# self-balan.net
KiCad netlist of a schematic drawn in EAGLE
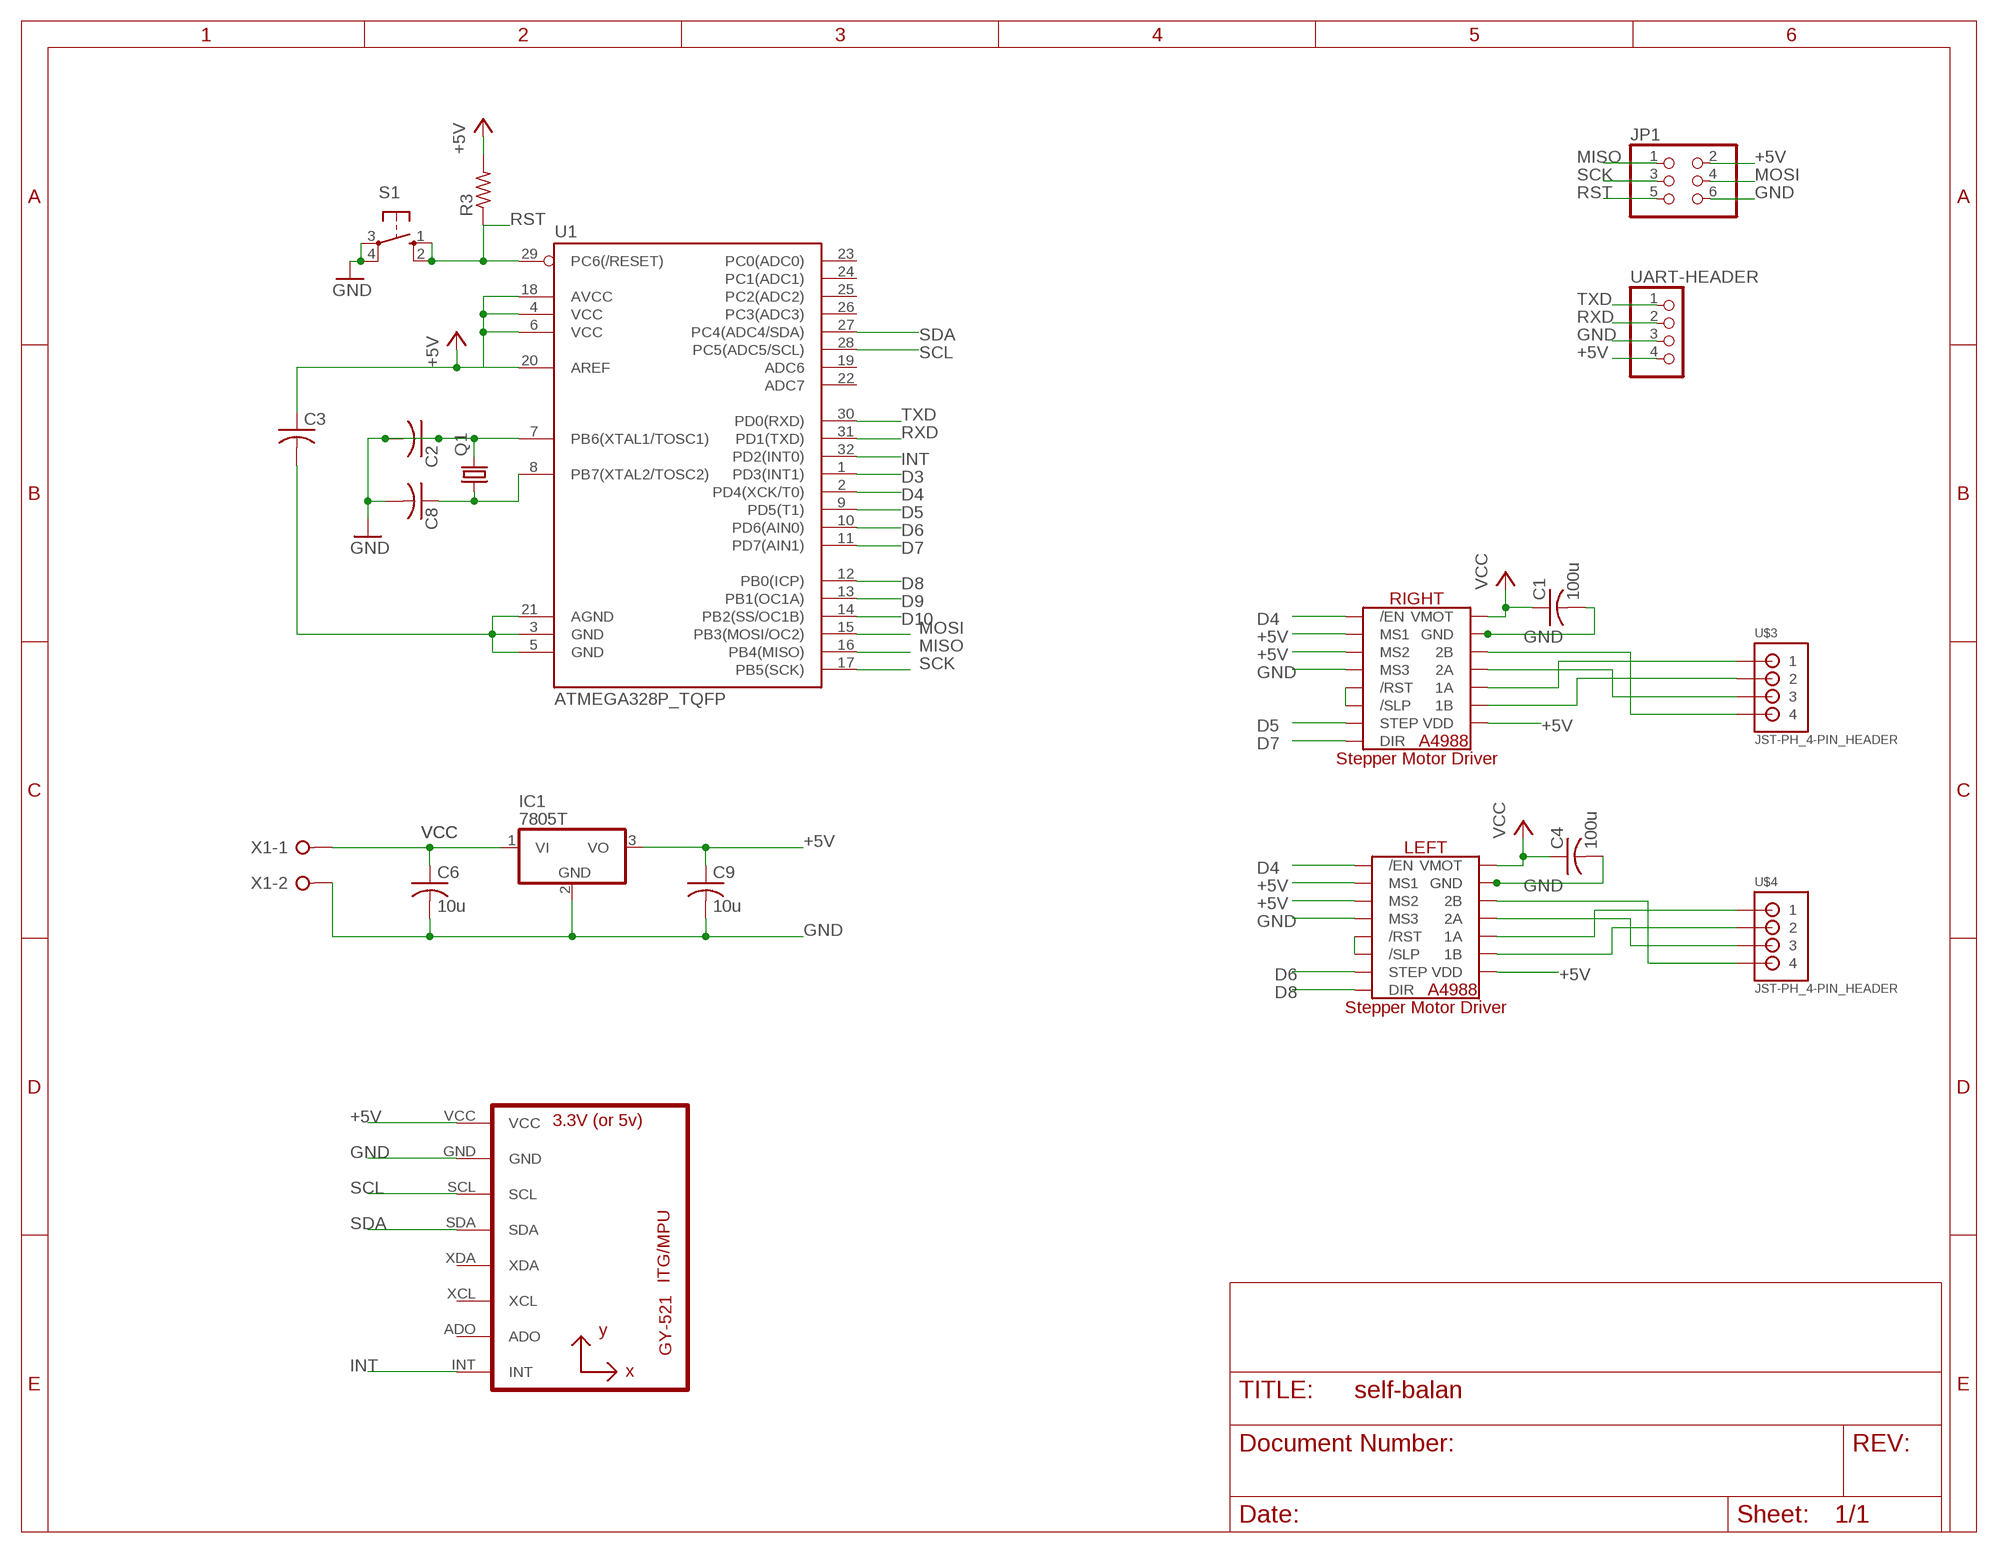
[diagram p0: schematic, sheet 1]

(export (version "E")
  (design (tool "Eeschema 10.0.6"))
  (components
    (comp (ref "C1")
      (value "100u")
      (footprint "eagle-import:C0805")
      (libsource (lib "eagle-import") (part "C-USC0805"))
    )
    (comp (ref "C2")
      (value "C-USC0805")
      (footprint "eagle-import:C0805")
      (libsource (lib "eagle-import") (part "C-USC0805"))
    )
    (comp (ref "C3")
      (value "C-USC0805")
      (footprint "eagle-import:C0805")
      (libsource (lib "eagle-import") (part "C-USC0805"))
    )
    (comp (ref "C4")
      (value "100u")
      (footprint "eagle-import:C0805")
      (libsource (lib "eagle-import") (part "C-USC0805"))
    )
    (comp (ref "C6")
      (value "10u")
      (footprint "eagle-import:C0805")
      (libsource (lib "eagle-import") (part "C-USC0805"))
    )
    (comp (ref "C8")
      (value "C-USC0805")
      (footprint "eagle-import:C0805")
      (libsource (lib "eagle-import") (part "C-USC0805"))
    )
    (comp (ref "C9")
      (value "10u")
      (footprint "eagle-import:C0805")
      (libsource (lib "eagle-import") (part "C-USC0805"))
    )
    (comp (ref "IC1")
      (value "7805T")
      (footprint "eagle-import:TO220H")
      (libsource (lib "eagle-import") (part "78T05"))
    )
    (comp (ref "JP1")
      (value "PINHD-2X3")
      (footprint "eagle-import:2X03")
      (libsource (lib "eagle-import") (part "PINHD-2X3"))
    )
    (comp (ref "LEFT")
      (value "A4988_STEP")
      (footprint "eagle-import:A4988_STEP")
      (libsource (lib "eagle-import") (part "A4988_STEP"))
    )
    (comp (ref "Q1")
      (value "CRYSTALHC18U-V")
      (footprint "eagle-import:HC18U-V")
      (libsource (lib "eagle-import") (part "CRYSTALHC18U-V"))
    )
    (comp (ref "R3")
      (value "R-US_R0805")
      (footprint "eagle-import:R0805")
      (libsource (lib "eagle-import") (part "R-US_R0805"))
    )
    (comp (ref "RIGHT")
      (value "A4988_STEP")
      (footprint "eagle-import:A4988_STEP")
      (libsource (lib "eagle-import") (part "A4988_STEP"))
    )
    (comp (ref "S1")
      (value "10-XX")
      (footprint "eagle-import:B3F-10XX")
      (fields (field (name "MPN") "B3F-1000"))
      (libsource (lib "eagle-import") (part "10-XX"))
    )
    (comp (ref "U$3")
      (value "JST-PH_4-PIN_HEADER")
      (footprint "eagle-import:JST_B4B-PH_HEADER")
      (libsource (lib "eagle-import") (part "JST-PH_4-PIN_HEADER"))
    )
    (comp (ref "U$4")
      (value "JST-PH_4-PIN_HEADER")
      (footprint "eagle-import:JST_B4B-PH_HEADER")
      (libsource (lib "eagle-import") (part "JST-PH_4-PIN_HEADER"))
    )
    (comp (ref "U1")
      (value "ATMEGA328P_TQFP")
      (footprint "eagle-import:TQFP32-08")
      (libsource (lib "eagle-import") (part "ATMEGA328P_TQFP"))
    )
    (comp (ref "U2")
      (value "GY-521MPU6050")
      (footprint "eagle-import:GY-521")
      (libsource (lib "eagle-import") (part "GY-521MPU6050"))
    )
    (comp (ref "UART-HEADER")
      (value "PINHD-1X4")
      (footprint "eagle-import:1X04")
      (libsource (lib "eagle-import") (part "PINHD-1X4"))
    )
    (comp (ref "X1")
      (value "W237-02P")
      (footprint "eagle-import:W237-132")
      (libsource (lib "eagle-import") (part "W237-02P"))
    )
  )
  (nets
    (net (code "1") (name "+5V") (class "Default")
      (node (ref "C3") (pin "1") (pinfunction "1_1") (pintype "passive"))
      (node (ref "C9") (pin "1") (pinfunction "1_1") (pintype "passive"))
      (node (ref "IC1") (pin "3") (pinfunction "VO_3") (pintype "passive"))
      (node (ref "JP1") (pin "2") (pinfunction "2_2") (pintype "passive"))
      (node (ref "LEFT") (pin "MS1") (pinfunction "MS1_MS1") (pintype "bidirectional"))
      (node (ref "LEFT") (pin "MS2") (pinfunction "MS2_MS2") (pintype "bidirectional"))
      (node (ref "LEFT") (pin "VDD") (pinfunction "VDD_VDD") (pintype "bidirectional"))
      (node (ref "R3") (pin "2") (pinfunction "2_2") (pintype "passive"))
      (node (ref "RIGHT") (pin "MS1") (pinfunction "MS1_MS1") (pintype "bidirectional"))
      (node (ref "RIGHT") (pin "MS2") (pinfunction "MS2_MS2") (pintype "bidirectional"))
      (node (ref "RIGHT") (pin "VDD") (pinfunction "VDD_VDD") (pintype "bidirectional"))
      (node (ref "U1") (pin "18") (pinfunction "AVCC_18") (pintype "bidirectional"))
      (node (ref "U1") (pin "20") (pinfunction "AREF_20") (pintype "bidirectional"))
      (node (ref "U1") (pin "4") (pinfunction "VCC_4") (pintype "bidirectional"))
      (node (ref "U1") (pin "6") (pinfunction "VCC_6") (pintype "bidirectional"))
      (node (ref "U2") (pin "VCC") (pinfunction "VCC_VCC") (pintype "bidirectional"))
      (node (ref "UART-HEADER") (pin "4") (pinfunction "4_4") (pintype "passive"))
    )
    (net (code "2") (name "/D3") (class "Default")
      (node (ref "U1") (pin "1") (pinfunction "PD3(INT1)_1") (pintype "bidirectional"))
    )
    (net (code "3") (name "/D4") (class "Default")
      (node (ref "LEFT") (pin "/EN") (pinfunction "/EN_/EN") (pintype "bidirectional"))
      (node (ref "RIGHT") (pin "/EN") (pinfunction "/EN_/EN") (pintype "bidirectional"))
      (node (ref "U1") (pin "2") (pinfunction "PD4(XCK/T0)_2") (pintype "bidirectional"))
    )
    (net (code "4") (name "/D5") (class "Default")
      (node (ref "RIGHT") (pin "STEP") (pinfunction "STEP_STEP") (pintype "bidirectional"))
      (node (ref "U1") (pin "9") (pinfunction "PD5(T1)_9") (pintype "bidirectional"))
    )
    (net (code "5") (name "/D6") (class "Default")
      (node (ref "LEFT") (pin "STEP") (pinfunction "STEP_STEP") (pintype "bidirectional"))
      (node (ref "U1") (pin "10") (pinfunction "PD6(AIN0)_10") (pintype "bidirectional"))
    )
    (net (code "6") (name "/D7") (class "Default")
      (node (ref "RIGHT") (pin "DIR") (pinfunction "DIR_DIR") (pintype "bidirectional"))
      (node (ref "U1") (pin "11") (pinfunction "PD7(AIN1)_11") (pintype "bidirectional"))
    )
    (net (code "7") (name "/D8") (class "Default")
      (node (ref "LEFT") (pin "DIR") (pinfunction "DIR_DIR") (pintype "bidirectional"))
      (node (ref "U1") (pin "12") (pinfunction "PB0(ICP)_12") (pintype "bidirectional"))
    )
    (net (code "8") (name "/D9") (class "Default")
      (node (ref "U1") (pin "13") (pinfunction "PB1(OC1A)_13") (pintype "bidirectional"))
    )
    (net (code "9") (name "/D10") (class "Default")
      (node (ref "U1") (pin "14") (pinfunction "PB2(SS/OC1B)_14") (pintype "bidirectional"))
    )
    (net (code "10") (name "/INT") (class "Default")
      (node (ref "U1") (pin "32") (pinfunction "PD2(INT0)_32") (pintype "bidirectional"))
      (node (ref "U2") (pin "INT") (pinfunction "INT_INT") (pintype "bidirectional"))
    )
    (net (code "11") (name "/MISO") (class "Default")
      (node (ref "JP1") (pin "1") (pinfunction "1_1") (pintype "passive"))
      (node (ref "U1") (pin "16") (pinfunction "PB4(MISO)_16") (pintype "bidirectional"))
    )
    (net (code "12") (name "/MOSI") (class "Default")
      (node (ref "JP1") (pin "4") (pinfunction "4_4") (pintype "passive"))
      (node (ref "U1") (pin "15") (pinfunction "PB3(MOSI/OC2)_15") (pintype "bidirectional"))
    )
    (net (code "13") (name "/RST") (class "Default")
      (node (ref "JP1") (pin "5") (pinfunction "5_5") (pintype "passive"))
      (node (ref "R3") (pin "1") (pinfunction "1_1") (pintype "passive"))
      (node (ref "S1") (pin "1") (pinfunction "S_1") (pintype "passive"))
      (node (ref "S1") (pin "2") (pinfunction "S1_2") (pintype "passive"))
      (node (ref "U1") (pin "29") (pinfunction "PC6(/RESET)_29") (pintype "bidirectional"))
    )
    (net (code "14") (name "/RXD") (class "Default")
      (node (ref "U1") (pin "31") (pinfunction "PD1(TXD)_31") (pintype "bidirectional"))
      (node (ref "UART-HEADER") (pin "2") (pinfunction "2_2") (pintype "passive"))
    )
    (net (code "15") (name "/SCK") (class "Default")
      (node (ref "JP1") (pin "3") (pinfunction "3_3") (pintype "passive"))
      (node (ref "U1") (pin "17") (pinfunction "PB5(SCK)_17") (pintype "bidirectional"))
    )
    (net (code "16") (name "/SCL") (class "Default")
      (node (ref "U1") (pin "28") (pinfunction "PC5(ADC5/SCL)_28") (pintype "bidirectional"))
      (node (ref "U2") (pin "SCL") (pinfunction "SCL_SCL") (pintype "bidirectional"))
    )
    (net (code "17") (name "/SDA") (class "Default")
      (node (ref "U1") (pin "27") (pinfunction "PC4(ADC4/SDA)_27") (pintype "bidirectional"))
      (node (ref "U2") (pin "SDA") (pinfunction "SDA_SDA") (pintype "bidirectional"))
    )
    (net (code "18") (name "/TXD") (class "Default")
      (node (ref "U1") (pin "30") (pinfunction "PD0(RXD)_30") (pintype "bidirectional"))
      (node (ref "UART-HEADER") (pin "1") (pinfunction "1_1") (pintype "passive"))
    )
    (net (code "19") (name "GND") (class "Default")
      (node (ref "C1") (pin "2") (pinfunction "2_2") (pintype "passive"))
      (node (ref "C2") (pin "1") (pinfunction "1_1") (pintype "passive"))
      (node (ref "C2") (pin "2") (pinfunction "2_2") (pintype "passive"))
      (node (ref "C4") (pin "2") (pinfunction "2_2") (pintype "passive"))
      (node (ref "C6") (pin "2") (pinfunction "2_2") (pintype "passive"))
      (node (ref "C8") (pin "2") (pinfunction "2_2") (pintype "passive"))
      (node (ref "C9") (pin "2") (pinfunction "2_2") (pintype "passive"))
      (node (ref "IC1") (pin "2") (pinfunction "GND_2") (pintype "passive"))
      (node (ref "JP1") (pin "6") (pinfunction "6_6") (pintype "passive"))
      (node (ref "LEFT") (pin "GND") (pinfunction "GND_GND") (pintype "bidirectional"))
      (node (ref "LEFT") (pin "GND2") (pinfunction "GND_GND2") (pintype "bidirectional"))
      (node (ref "LEFT") (pin "MS3") (pinfunction "MS3_MS3") (pintype "bidirectional"))
      (node (ref "Q1") (pin "2") (pinfunction "2_2") (pintype "passive"))
      (node (ref "RIGHT") (pin "GND") (pinfunction "GND_GND") (pintype "bidirectional"))
      (node (ref "RIGHT") (pin "GND2") (pinfunction "GND_GND2") (pintype "bidirectional"))
      (node (ref "RIGHT") (pin "MS3") (pinfunction "MS3_MS3") (pintype "bidirectional"))
      (node (ref "S1") (pin "3") (pinfunction "P_3") (pintype "passive"))
      (node (ref "S1") (pin "4") (pinfunction "P1_4") (pintype "passive"))
      (node (ref "U1") (pin "7") (pinfunction "PB6(XTAL1/TOSC1)_7") (pintype "bidirectional"))
      (node (ref "U2") (pin "GND") (pinfunction "GND_GND") (pintype "bidirectional"))
      (node (ref "UART-HEADER") (pin "3") (pinfunction "3_3") (pintype "passive"))
      (node (ref "X1") (pin "2") (pinfunction "KL_2") (pintype "passive"))
    )
    (net (code "20") (name "Net-(LEFT-Pad{slash}RST)") (class "Default")
      (node (ref "LEFT") (pin "/RST") (pinfunction "/RST_/RST") (pintype "bidirectional"))
      (node (ref "LEFT") (pin "/SLP") (pinfunction "/SLP_/SLP") (pintype "bidirectional"))
    )
    (net (code "21") (name "Net-(RIGHT-Pad{slash}RST)") (class "Default")
      (node (ref "RIGHT") (pin "/RST") (pinfunction "/RST_/RST") (pintype "bidirectional"))
      (node (ref "RIGHT") (pin "/SLP") (pinfunction "/SLP_/SLP") (pintype "bidirectional"))
    )
    (net (code "22") (name "Net-(U$3-1)") (class "Default")
      (node (ref "RIGHT") (pin "1A") (pinfunction "1A_1A") (pintype "bidirectional"))
      (node (ref "U$3") (pin "P1") (pinfunction "1_P1") (pintype "bidirectional"))
    )
    (net (code "23") (name "Net-(U$3-2)") (class "Default")
      (node (ref "RIGHT") (pin "1B") (pinfunction "1B_1B") (pintype "bidirectional"))
      (node (ref "U$3") (pin "P2") (pinfunction "2_P2") (pintype "bidirectional"))
    )
    (net (code "24") (name "Net-(U$3-3)") (class "Default")
      (node (ref "RIGHT") (pin "2A") (pinfunction "2A_2A") (pintype "bidirectional"))
      (node (ref "U$3") (pin "P3") (pinfunction "3_P3") (pintype "bidirectional"))
    )
    (net (code "25") (name "Net-(U$3-4)") (class "Default")
      (node (ref "RIGHT") (pin "2B") (pinfunction "2B_2B") (pintype "bidirectional"))
      (node (ref "U$3") (pin "P4") (pinfunction "4_P4") (pintype "bidirectional"))
    )
    (net (code "26") (name "Net-(U$4-1)") (class "Default")
      (node (ref "LEFT") (pin "1A") (pinfunction "1A_1A") (pintype "bidirectional"))
      (node (ref "U$4") (pin "P1") (pinfunction "1_P1") (pintype "bidirectional"))
    )
    (net (code "27") (name "Net-(U$4-2)") (class "Default")
      (node (ref "LEFT") (pin "1B") (pinfunction "1B_1B") (pintype "bidirectional"))
      (node (ref "U$4") (pin "P2") (pinfunction "2_P2") (pintype "bidirectional"))
    )
    (net (code "28") (name "Net-(U$4-3)") (class "Default")
      (node (ref "LEFT") (pin "2A") (pinfunction "2A_2A") (pintype "bidirectional"))
      (node (ref "U$4") (pin "P3") (pinfunction "3_P3") (pintype "bidirectional"))
    )
    (net (code "29") (name "Net-(U$4-4)") (class "Default")
      (node (ref "LEFT") (pin "2B") (pinfunction "2B_2B") (pintype "bidirectional"))
      (node (ref "U$4") (pin "P4") (pinfunction "4_P4") (pintype "bidirectional"))
    )
    (net (code "30") (name "Net-(U1-AGND)") (class "Default")
      (node (ref "C3") (pin "2") (pinfunction "2_2") (pintype "passive"))
      (node (ref "U1") (pin "21") (pinfunction "AGND_21") (pintype "bidirectional"))
      (node (ref "U1") (pin "3") (pinfunction "GND_3") (pintype "bidirectional"))
      (node (ref "U1") (pin "5") (pinfunction "GND_5") (pintype "bidirectional"))
    )
    (net (code "31") (name "Net-(U1-PB7(XTAL2{slash}TOSC2))") (class "Default")
      (node (ref "C8") (pin "1") (pinfunction "1_1") (pintype "passive"))
      (node (ref "Q1") (pin "1") (pinfunction "1_1") (pintype "passive"))
      (node (ref "U1") (pin "8") (pinfunction "PB7(XTAL2/TOSC2)_8") (pintype "bidirectional"))
    )
    (net (code "32") (name "VCC") (class "Default")
      (node (ref "C1") (pin "1") (pinfunction "1_1") (pintype "passive"))
      (node (ref "C4") (pin "1") (pinfunction "1_1") (pintype "passive"))
      (node (ref "C6") (pin "1") (pinfunction "1_1") (pintype "passive"))
      (node (ref "IC1") (pin "1") (pinfunction "VI_1") (pintype "input"))
      (node (ref "LEFT") (pin "VMOT") (pinfunction "VMOT_VMOT") (pintype "bidirectional"))
      (node (ref "RIGHT") (pin "VMOT") (pinfunction "VMOT_VMOT") (pintype "bidirectional"))
      (node (ref "X1") (pin "1") (pinfunction "KL_1") (pintype "passive"))
    )
    (net (code "33") (name "unconnected-(U1-ADC6-Pad19)") (class "Default")
      (node (ref "U1") (pin "19") (pinfunction "ADC6_19") (pintype "bidirectional"))
    )
    (net (code "34") (name "unconnected-(U1-ADC7-Pad22)") (class "Default")
      (node (ref "U1") (pin "22") (pinfunction "ADC7_22") (pintype "bidirectional"))
    )
    (net (code "35") (name "unconnected-(U1-PC0(ADC0)-Pad23)") (class "Default")
      (node (ref "U1") (pin "23") (pinfunction "PC0(ADC0)_23") (pintype "bidirectional"))
    )
    (net (code "36") (name "unconnected-(U1-PC1(ADC1)-Pad24)") (class "Default")
      (node (ref "U1") (pin "24") (pinfunction "PC1(ADC1)_24") (pintype "bidirectional"))
    )
    (net (code "37") (name "unconnected-(U1-PC2(ADC2)-Pad25)") (class "Default")
      (node (ref "U1") (pin "25") (pinfunction "PC2(ADC2)_25") (pintype "bidirectional"))
    )
    (net (code "38") (name "unconnected-(U1-PC3(ADC3)-Pad26)") (class "Default")
      (node (ref "U1") (pin "26") (pinfunction "PC3(ADC3)_26") (pintype "bidirectional"))
    )
    (net (code "39") (name "unconnected-(U2-PadADO)") (class "Default")
      (node (ref "U2") (pin "ADO") (pinfunction "ADO_ADO") (pintype "bidirectional"))
    )
    (net (code "40") (name "unconnected-(U2-PadXCL)") (class "Default")
      (node (ref "U2") (pin "XCL") (pinfunction "XCL_XCL") (pintype "bidirectional"))
    )
    (net (code "41") (name "unconnected-(U2-PadXDA)") (class "Default")
      (node (ref "U2") (pin "XDA") (pinfunction "XDA_XDA") (pintype "bidirectional"))
    )
  )
)
